# Connectors_and_mechanical.net
KiCad netlist of a schematic drawn in Altium Designer
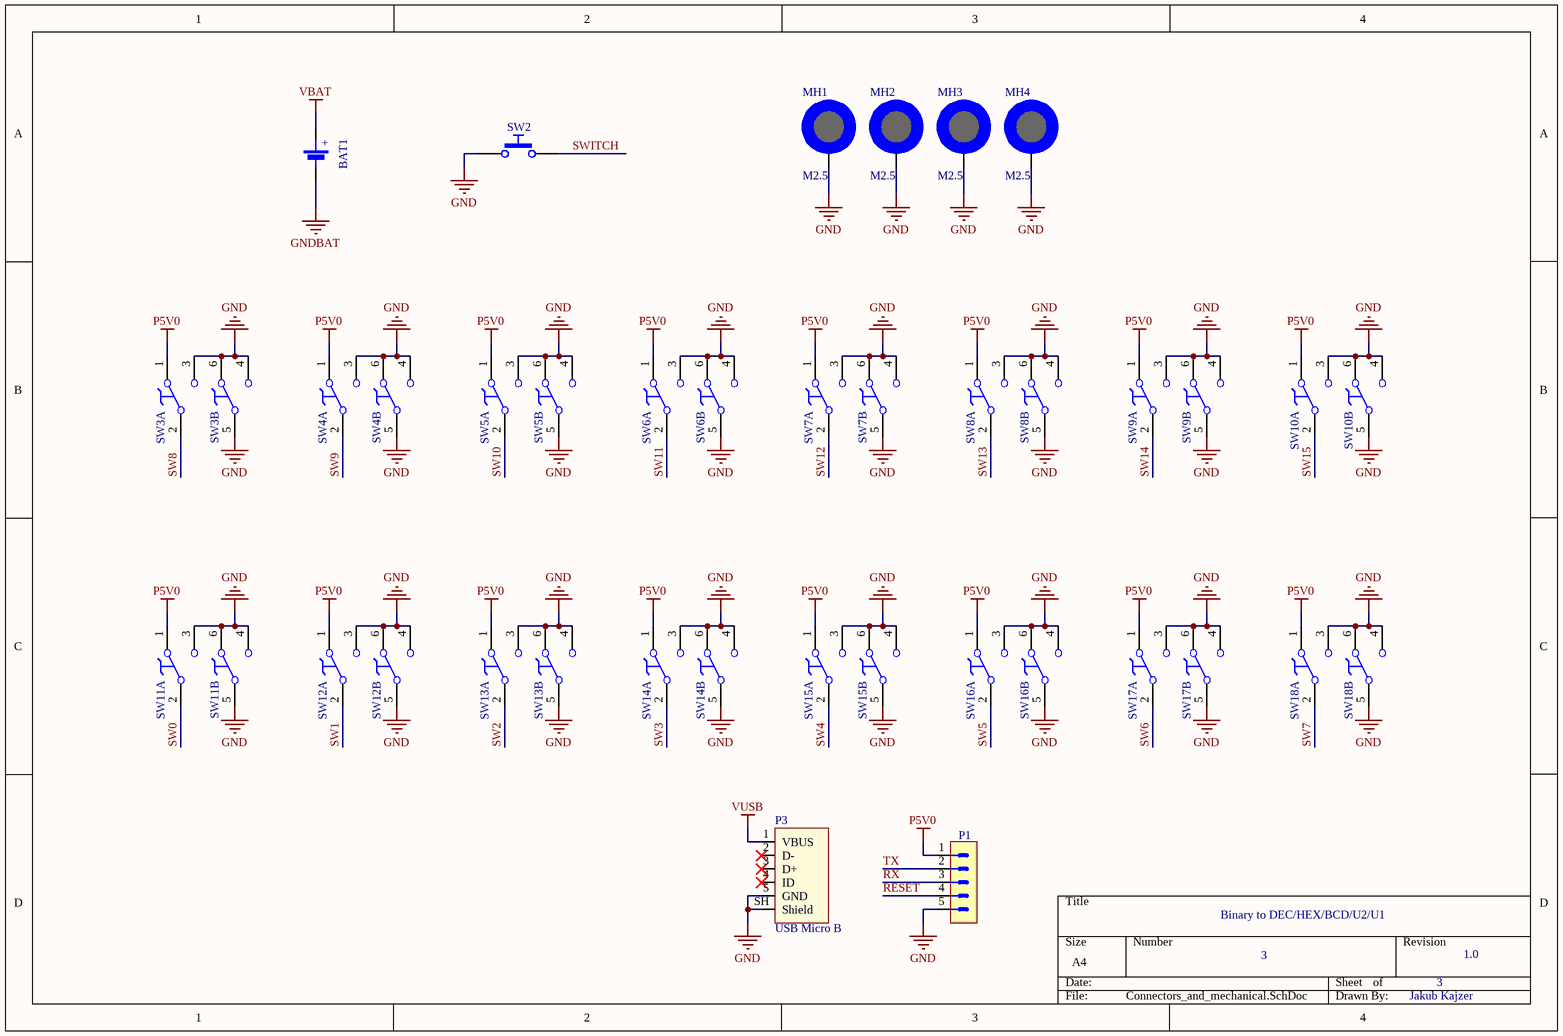
[diagram p0: Connectors_and_mechanical.SchDoc]

(export (version "E")
  (design (tool "Eeschema 10.0.6"))
  (components
    (comp (ref "BAT1")
      (value "~")
      (footprint "18650 Holder")
      (description "18650 Cell Battery Holder")
      (fields
        (field (name "MANUFACTURER") "GENERIC")
        (field (name "MANUFACTURER PART NUMBER") "18650 Holder")
        (field (name "AUTHOR") "JK")
      )
      (libsource (lib "Connectors") (part "BAT-HLD-001"))
    )
    (comp (ref "MH1")
      (value "M2.5")
      (footprint "MH-M2.5_COPPER")
      (description "Mounting hole, M2.5, exposed pad")
      (fields (field (name "AUTHOR") "KB"))
      (libsource (lib "Mechanical And PCB Features") (part "MH"))
    )
    (comp (ref "MH2")
      (value "M2.5")
      (footprint "MH-M2.5_COPPER")
      (description "Mounting hole, M2.5, exposed pad")
      (fields (field (name "AUTHOR") "KB"))
      (libsource (lib "Mechanical And PCB Features") (part "MH"))
    )
    (comp (ref "MH3")
      (value "M2.5")
      (footprint "MH-M2.5_COPPER")
      (description "Mounting hole, M2.5, exposed pad")
      (fields (field (name "AUTHOR") "KB"))
      (libsource (lib "Mechanical And PCB Features") (part "MH"))
    )
    (comp (ref "MH4")
      (value "M2.5")
      (footprint "MH-M2.5_COPPER")
      (description "Mounting hole, M2.5, exposed pad")
      (fields (field (name "AUTHOR") "KB"))
      (libsource (lib "Mechanical And PCB Features") (part "MH"))
    )
    (comp (ref "P1")
      (value "SSW-105-02-G-S")
      (footprint "SAMTEC_SSW-105-02-G-S")
      (description "General Purpose Header: THT, 2.54mm, Female, Straight, Long Lead")
      (fields
        (field (name "MANUFACTURER") "GENERIC")
        (field (name "MANUFACTURER PART NUMBER") "HDR_THT_5X1V_F_2P54MM")
        (field (name "AUTHOR") "UN")
      )
      (libsource (lib "Connectors") (part "Header 5x1"))
    )
    (comp (ref "P3")
      (value "USB Micro B")
      (footprint "USB Micro")
      (description "USB B micro; SMT; PIN: 5; Horizontal; V: USB 2.0")
      (fields
        (field (name "MANUFACTURER") "AMPHENOL")
        (field (name "MANUFACTURER PART NUMBER") "10118192-0001LF")
        (field (name "AUTHOR") "JK")
      )
      (libsource (lib "Connectors") (part "USB_5pin+Shield"))
    )
    (comp (ref "SW2")
      (value "PTS636")
      (footprint "PTS636_SMT_G")
      (description "Tactile Switches Tact 50mA 12VDC, 6.0x3.5, 4.3mm H, 180gf, G leads, No ground pin, Black Actuator")
      (fields
        (field (name "MANUFACTURER") "C&K")
        (field (name "MANUFACTURER PART NUMBER") "PTS636 SM43 SMTR LFS")
        (field (name "AUTHOR") "KB")
      )
      (libsource (lib "Relays And Switches") (part "PB SPST 1NO-2NO"))
    )
    (comp (ref "SW3")
      (value "SS008B")
      (footprint "SS008B-02P-22")
      (description "Switch  2 position; DPDT; 0,3A/30VDC; ON-ON; 50mŁ[")
      (fields
        (field (name "MANUFACTURER") "CANAL ELECTRONIC")
        (field (name "MANUFACTURER PART NUMBER") "SS008B-02P-22")
        (field (name "AUTHOR") "JK")
      )
      (libsource (lib "") (part "SW DPDT 1NC-2C-3NO-4NO-5C-6NC_1"))
    )
    (comp (ref "SW4")
      (value "SS008B")
      (footprint "SS008B-02P-22")
      (description "Switch  2 position; DPDT; 0,3A/30VDC; ON-ON; 50mŁ[")
      (fields
        (field (name "MANUFACTURER") "CANAL ELECTRONIC")
        (field (name "MANUFACTURER PART NUMBER") "SS008B-02P-22")
        (field (name "AUTHOR") "JK")
      )
      (libsource (lib "") (part "SW DPDT 1NC-2C-3NO-4NO-5C-6NC_1"))
    )
    (comp (ref "SW5")
      (value "SS008B")
      (footprint "SS008B-02P-22")
      (description "Switch  2 position; DPDT; 0,3A/30VDC; ON-ON; 50mŁ[")
      (fields
        (field (name "MANUFACTURER") "CANAL ELECTRONIC")
        (field (name "MANUFACTURER PART NUMBER") "SS008B-02P-22")
        (field (name "AUTHOR") "JK")
      )
      (libsource (lib "Relays And Switches") (part "SW DPDT 1NC-2C-3NO-4NO-5C-6NC"))
    )
    (comp (ref "SW6")
      (value "SS008B")
      (footprint "SS008B-02P-22")
      (description "Switch  2 position; DPDT; 0,3A/30VDC; ON-ON; 50mŁ[")
      (fields
        (field (name "MANUFACTURER") "CANAL ELECTRONIC")
        (field (name "MANUFACTURER PART NUMBER") "SS008B-02P-22")
        (field (name "AUTHOR") "JK")
      )
      (libsource (lib "Relays And Switches") (part "SW DPDT 1NC-2C-3NO-4NO-5C-6NC"))
    )
    (comp (ref "SW7")
      (value "SS008B")
      (footprint "SS008B-02P-22")
      (description "Switch  2 position; DPDT; 0,3A/30VDC; ON-ON; 50mŁ[")
      (fields
        (field (name "MANUFACTURER") "CANAL ELECTRONIC")
        (field (name "MANUFACTURER PART NUMBER") "SS008B-02P-22")
        (field (name "AUTHOR") "JK")
      )
      (libsource (lib "") (part "SW DPDT 1NC-2C-3NO-4NO-5C-6NC_1"))
    )
    (comp (ref "SW8")
      (value "SS008B")
      (footprint "SS008B-02P-22")
      (description "Switch  2 position; DPDT; 0,3A/30VDC; ON-ON; 50mŁ[")
      (fields
        (field (name "MANUFACTURER") "CANAL ELECTRONIC")
        (field (name "MANUFACTURER PART NUMBER") "SS008B-02P-22")
        (field (name "AUTHOR") "JK")
      )
      (libsource (lib "Relays And Switches") (part "SW DPDT 1NC-2C-3NO-4NO-5C-6NC"))
    )
    (comp (ref "SW9")
      (value "SS008B")
      (footprint "SS008B-02P-22")
      (description "Switch  2 position; DPDT; 0,3A/30VDC; ON-ON; 50mŁ[")
      (fields
        (field (name "MANUFACTURER") "CANAL ELECTRONIC")
        (field (name "MANUFACTURER PART NUMBER") "SS008B-02P-22")
        (field (name "AUTHOR") "JK")
      )
      (libsource (lib "Relays And Switches") (part "SW DPDT 1NC-2C-3NO-4NO-5C-6NC"))
    )
    (comp (ref "SW10")
      (value "SS008B")
      (footprint "SS008B-02P-22")
      (description "Switch  2 position; DPDT; 0,3A/30VDC; ON-ON; 50mŁ[")
      (fields
        (field (name "MANUFACTURER") "CANAL ELECTRONIC")
        (field (name "MANUFACTURER PART NUMBER") "SS008B-02P-22")
        (field (name "AUTHOR") "JK")
      )
      (libsource (lib "Relays And Switches") (part "SW DPDT 1NC-2C-3NO-4NO-5C-6NC"))
    )
    (comp (ref "SW11")
      (value "SS008B")
      (footprint "SS008B-02P-22")
      (description "Switch  2 position; DPDT; 0,3A/30VDC; ON-ON; 50mŁ[")
      (fields
        (field (name "MANUFACTURER") "CANAL ELECTRONIC")
        (field (name "MANUFACTURER PART NUMBER") "SS008B-02P-22")
        (field (name "AUTHOR") "JK")
      )
      (libsource (lib "Relays And Switches") (part "SW DPDT 1NC-2C-3NO-4NO-5C-6NC"))
    )
    (comp (ref "SW12")
      (value "SS008B")
      (footprint "SS008B-02P-22")
      (description "Switch  2 position; DPDT; 0,3A/30VDC; ON-ON; 50mŁ[")
      (fields
        (field (name "MANUFACTURER") "CANAL ELECTRONIC")
        (field (name "MANUFACTURER PART NUMBER") "SS008B-02P-22")
        (field (name "AUTHOR") "JK")
      )
      (libsource (lib "Relays And Switches") (part "SW DPDT 1NC-2C-3NO-4NO-5C-6NC"))
    )
    (comp (ref "SW13")
      (value "SS008B")
      (footprint "SS008B-02P-22")
      (description "Switch  2 position; DPDT; 0,3A/30VDC; ON-ON; 50mŁ[")
      (fields
        (field (name "MANUFACTURER") "CANAL ELECTRONIC")
        (field (name "MANUFACTURER PART NUMBER") "SS008B-02P-22")
        (field (name "AUTHOR") "JK")
      )
      (libsource (lib "") (part "SW DPDT 1NC-2C-3NO-4NO-5C-6NC_1"))
    )
    (comp (ref "SW14")
      (value "SS008B")
      (footprint "SS008B-02P-22")
      (description "Switch  2 position; DPDT; 0,3A/30VDC; ON-ON; 50mŁ[")
      (fields
        (field (name "MANUFACTURER") "CANAL ELECTRONIC")
        (field (name "MANUFACTURER PART NUMBER") "SS008B-02P-22")
        (field (name "AUTHOR") "JK")
      )
      (libsource (lib "") (part "SW DPDT 1NC-2C-3NO-4NO-5C-6NC_1"))
    )
    (comp (ref "SW15")
      (value "SS008B")
      (footprint "SS008B-02P-22")
      (description "Switch  2 position; DPDT; 0,3A/30VDC; ON-ON; 50mŁ[")
      (fields
        (field (name "MANUFACTURER") "CANAL ELECTRONIC")
        (field (name "MANUFACTURER PART NUMBER") "SS008B-02P-22")
        (field (name "AUTHOR") "JK")
      )
      (libsource (lib "Relays And Switches") (part "SW DPDT 1NC-2C-3NO-4NO-5C-6NC"))
    )
    (comp (ref "SW16")
      (value "SS008B")
      (footprint "SS008B-02P-22")
      (description "Switch  2 position; DPDT; 0,3A/30VDC; ON-ON; 50mŁ[")
      (fields
        (field (name "MANUFACTURER") "CANAL ELECTRONIC")
        (field (name "MANUFACTURER PART NUMBER") "SS008B-02P-22")
        (field (name "AUTHOR") "JK")
      )
      (libsource (lib "Relays And Switches") (part "SW DPDT 1NC-2C-3NO-4NO-5C-6NC"))
    )
    (comp (ref "SW17")
      (value "SS008B")
      (footprint "SS008B-02P-22")
      (description "Switch  2 position; DPDT; 0,3A/30VDC; ON-ON; 50mŁ[")
      (fields
        (field (name "MANUFACTURER") "CANAL ELECTRONIC")
        (field (name "MANUFACTURER PART NUMBER") "SS008B-02P-22")
        (field (name "AUTHOR") "JK")
      )
      (libsource (lib "") (part "SW DPDT 1NC-2C-3NO-4NO-5C-6NC_1"))
    )
    (comp (ref "SW18")
      (value "SS008B")
      (footprint "SS008B-02P-22")
      (description "Switch  2 position; DPDT; 0,3A/30VDC; ON-ON; 50mŁ[")
      (fields
        (field (name "MANUFACTURER") "CANAL ELECTRONIC")
        (field (name "MANUFACTURER PART NUMBER") "SS008B-02P-22")
        (field (name "AUTHOR") "JK")
      )
      (libsource (lib "Relays And Switches") (part "SW DPDT 1NC-2C-3NO-4NO-5C-6NC"))
    )
  )
  (nets
    (net (code "1") (name "/RESET") (class "Default")
      (node (ref "P1") (pin "4") (pinfunction "4_4") (pintype "passive"))
    )
    (net (code "2") (name "/RX") (class "Default")
      (node (ref "P1") (pin "3") (pinfunction "3_3") (pintype "passive"))
    )
    (net (code "3") (name "/SW0") (class "Default")
      (node (ref "SW11") (pin "2") (pinfunction "2_2") (pintype "passive"))
    )
    (net (code "4") (name "/SW1") (class "Default")
      (node (ref "SW12") (pin "2") (pinfunction "2_2") (pintype "passive"))
    )
    (net (code "5") (name "/SW2") (class "Default")
      (node (ref "SW13") (pin "2") (pinfunction "2_2") (pintype "passive"))
    )
    (net (code "6") (name "/SW3") (class "Default")
      (node (ref "SW14") (pin "2") (pinfunction "2_2") (pintype "passive"))
    )
    (net (code "7") (name "/SW4") (class "Default")
      (node (ref "SW15") (pin "2") (pinfunction "2_2") (pintype "passive"))
    )
    (net (code "8") (name "/SW5") (class "Default")
      (node (ref "SW16") (pin "2") (pinfunction "2_2") (pintype "passive"))
    )
    (net (code "9") (name "/SW6") (class "Default")
      (node (ref "SW17") (pin "2") (pinfunction "2_2") (pintype "passive"))
    )
    (net (code "10") (name "/SW7") (class "Default")
      (node (ref "SW18") (pin "2") (pinfunction "2_2") (pintype "passive"))
    )
    (net (code "11") (name "/SW8") (class "Default")
      (node (ref "SW3") (pin "2") (pinfunction "2_2") (pintype "passive"))
    )
    (net (code "12") (name "/SW9") (class "Default")
      (node (ref "SW4") (pin "2") (pinfunction "2_2") (pintype "passive"))
    )
    (net (code "13") (name "/SW10") (class "Default")
      (node (ref "SW5") (pin "2") (pinfunction "2_2") (pintype "passive"))
    )
    (net (code "14") (name "/SW11") (class "Default")
      (node (ref "SW6") (pin "2") (pinfunction "2_2") (pintype "passive"))
    )
    (net (code "15") (name "/SW12") (class "Default")
      (node (ref "SW7") (pin "2") (pinfunction "2_2") (pintype "passive"))
    )
    (net (code "16") (name "/SW13") (class "Default")
      (node (ref "SW8") (pin "2") (pinfunction "2_2") (pintype "passive"))
    )
    (net (code "17") (name "/SW14") (class "Default")
      (node (ref "SW9") (pin "2") (pinfunction "2_2") (pintype "passive"))
    )
    (net (code "18") (name "/SW15") (class "Default")
      (node (ref "SW10") (pin "2") (pinfunction "2_2") (pintype "passive"))
    )
    (net (code "19") (name "/SWITCH") (class "Default")
      (node (ref "SW2") (pin "2") (pinfunction "2_2") (pintype "passive"))
    )
    (net (code "20") (name "/TX") (class "Default")
      (node (ref "P1") (pin "2") (pinfunction "2_2") (pintype "passive"))
    )
    (net (code "21") (name "GND") (class "Default")
      (node (ref "MH1") (pin "MH") (pinfunction "MH_MH") (pintype "passive"))
      (node (ref "MH2") (pin "MH") (pinfunction "MH_MH") (pintype "passive"))
      (node (ref "MH3") (pin "MH") (pinfunction "MH_MH") (pintype "passive"))
      (node (ref "MH4") (pin "MH") (pinfunction "MH_MH") (pintype "passive"))
      (node (ref "P1") (pin "5") (pinfunction "5_5") (pintype "passive"))
      (node (ref "P3") (pin "5") (pinfunction "GND_5") (pintype "power_in"))
      (node (ref "P3") (pin "SH") (pinfunction "Shield_SH") (pintype "passive"))
      (node (ref "SW10") (pin "3") (pinfunction "3_3") (pintype "passive"))
      (node (ref "SW10") (pin "4") (pinfunction "4_4") (pintype "passive"))
      (node (ref "SW10") (pin "5") (pinfunction "5_5") (pintype "passive"))
      (node (ref "SW10") (pin "6") (pinfunction "6_6") (pintype "passive"))
      (node (ref "SW11") (pin "3") (pinfunction "3_3") (pintype "passive"))
      (node (ref "SW11") (pin "4") (pinfunction "4_4") (pintype "passive"))
      (node (ref "SW11") (pin "5") (pinfunction "5_5") (pintype "passive"))
      (node (ref "SW11") (pin "6") (pinfunction "6_6") (pintype "passive"))
      (node (ref "SW12") (pin "3") (pinfunction "3_3") (pintype "passive"))
      (node (ref "SW12") (pin "4") (pinfunction "4_4") (pintype "passive"))
      (node (ref "SW12") (pin "5") (pinfunction "5_5") (pintype "passive"))
      (node (ref "SW12") (pin "6") (pinfunction "6_6") (pintype "passive"))
      (node (ref "SW13") (pin "3") (pinfunction "3_3") (pintype "passive"))
      (node (ref "SW13") (pin "4") (pinfunction "4_4") (pintype "passive"))
      (node (ref "SW13") (pin "5") (pinfunction "5_5") (pintype "passive"))
      (node (ref "SW13") (pin "6") (pinfunction "6_6") (pintype "passive"))
      (node (ref "SW14") (pin "3") (pinfunction "3_3") (pintype "passive"))
      (node (ref "SW14") (pin "4") (pinfunction "4_4") (pintype "passive"))
      (node (ref "SW14") (pin "5") (pinfunction "5_5") (pintype "passive"))
      (node (ref "SW14") (pin "6") (pinfunction "6_6") (pintype "passive"))
      (node (ref "SW15") (pin "3") (pinfunction "3_3") (pintype "passive"))
      (node (ref "SW15") (pin "4") (pinfunction "4_4") (pintype "passive"))
      (node (ref "SW15") (pin "5") (pinfunction "5_5") (pintype "passive"))
      (node (ref "SW15") (pin "6") (pinfunction "6_6") (pintype "passive"))
      (node (ref "SW16") (pin "3") (pinfunction "3_3") (pintype "passive"))
      (node (ref "SW16") (pin "4") (pinfunction "4_4") (pintype "passive"))
      (node (ref "SW16") (pin "5") (pinfunction "5_5") (pintype "passive"))
      (node (ref "SW16") (pin "6") (pinfunction "6_6") (pintype "passive"))
      (node (ref "SW17") (pin "3") (pinfunction "3_3") (pintype "passive"))
      (node (ref "SW17") (pin "4") (pinfunction "4_4") (pintype "passive"))
      (node (ref "SW17") (pin "5") (pinfunction "5_5") (pintype "passive"))
      (node (ref "SW17") (pin "6") (pinfunction "6_6") (pintype "passive"))
      (node (ref "SW18") (pin "3") (pinfunction "3_3") (pintype "passive"))
      (node (ref "SW18") (pin "4") (pinfunction "4_4") (pintype "passive"))
      (node (ref "SW18") (pin "5") (pinfunction "5_5") (pintype "passive"))
      (node (ref "SW18") (pin "6") (pinfunction "6_6") (pintype "passive"))
      (node (ref "SW2") (pin "1") (pinfunction "1_1") (pintype "passive"))
      (node (ref "SW3") (pin "3") (pinfunction "3_3") (pintype "passive"))
      (node (ref "SW3") (pin "4") (pinfunction "4_4") (pintype "passive"))
      (node (ref "SW3") (pin "5") (pinfunction "5_5") (pintype "passive"))
      (node (ref "SW3") (pin "6") (pinfunction "6_6") (pintype "passive"))
      (node (ref "SW4") (pin "3") (pinfunction "3_3") (pintype "passive"))
      (node (ref "SW4") (pin "4") (pinfunction "4_4") (pintype "passive"))
      (node (ref "SW4") (pin "5") (pinfunction "5_5") (pintype "passive"))
      (node (ref "SW4") (pin "6") (pinfunction "6_6") (pintype "passive"))
      (node (ref "SW5") (pin "3") (pinfunction "3_3") (pintype "passive"))
      (node (ref "SW5") (pin "4") (pinfunction "4_4") (pintype "passive"))
      (node (ref "SW5") (pin "5") (pinfunction "5_5") (pintype "passive"))
      (node (ref "SW5") (pin "6") (pinfunction "6_6") (pintype "passive"))
      (node (ref "SW6") (pin "3") (pinfunction "3_3") (pintype "passive"))
      (node (ref "SW6") (pin "4") (pinfunction "4_4") (pintype "passive"))
      (node (ref "SW6") (pin "5") (pinfunction "5_5") (pintype "passive"))
      (node (ref "SW6") (pin "6") (pinfunction "6_6") (pintype "passive"))
      (node (ref "SW7") (pin "3") (pinfunction "3_3") (pintype "passive"))
      (node (ref "SW7") (pin "4") (pinfunction "4_4") (pintype "passive"))
      (node (ref "SW7") (pin "5") (pinfunction "5_5") (pintype "passive"))
      (node (ref "SW7") (pin "6") (pinfunction "6_6") (pintype "passive"))
      (node (ref "SW8") (pin "3") (pinfunction "3_3") (pintype "passive"))
      (node (ref "SW8") (pin "4") (pinfunction "4_4") (pintype "passive"))
      (node (ref "SW8") (pin "5") (pinfunction "5_5") (pintype "passive"))
      (node (ref "SW8") (pin "6") (pinfunction "6_6") (pintype "passive"))
      (node (ref "SW9") (pin "3") (pinfunction "3_3") (pintype "passive"))
      (node (ref "SW9") (pin "4") (pinfunction "4_4") (pintype "passive"))
      (node (ref "SW9") (pin "5") (pinfunction "5_5") (pintype "passive"))
      (node (ref "SW9") (pin "6") (pinfunction "6_6") (pintype "passive"))
    )
    (net (code "22") (name "GNDBAT") (class "Default")
      (node (ref "BAT1") (pin "1") (pinfunction "MINUS_1") (pintype "power_in"))
    )
    (net (code "23") (name "P5V0") (class "Default")
      (node (ref "P1") (pin "1") (pinfunction "1_1") (pintype "passive"))
      (node (ref "SW10") (pin "1") (pinfunction "1_1") (pintype "passive"))
      (node (ref "SW11") (pin "1") (pinfunction "1_1") (pintype "passive"))
      (node (ref "SW12") (pin "1") (pinfunction "1_1") (pintype "passive"))
      (node (ref "SW13") (pin "1") (pinfunction "1_1") (pintype "passive"))
      (node (ref "SW14") (pin "1") (pinfunction "1_1") (pintype "passive"))
      (node (ref "SW15") (pin "1") (pinfunction "1_1") (pintype "passive"))
      (node (ref "SW16") (pin "1") (pinfunction "1_1") (pintype "passive"))
      (node (ref "SW17") (pin "1") (pinfunction "1_1") (pintype "passive"))
      (node (ref "SW18") (pin "1") (pinfunction "1_1") (pintype "passive"))
      (node (ref "SW3") (pin "1") (pinfunction "1_1") (pintype "passive"))
      (node (ref "SW4") (pin "1") (pinfunction "1_1") (pintype "passive"))
      (node (ref "SW5") (pin "1") (pinfunction "1_1") (pintype "passive"))
      (node (ref "SW6") (pin "1") (pinfunction "1_1") (pintype "passive"))
      (node (ref "SW7") (pin "1") (pinfunction "1_1") (pintype "passive"))
      (node (ref "SW8") (pin "1") (pinfunction "1_1") (pintype "passive"))
      (node (ref "SW9") (pin "1") (pinfunction "1_1") (pintype "passive"))
    )
    (net (code "24") (name "VBAT") (class "Default")
      (node (ref "BAT1") (pin "2") (pinfunction "PLUS_2") (pintype "power_in"))
    )
    (net (code "25") (name "VUSB") (class "Default")
      (node (ref "P3") (pin "1") (pinfunction "VBUS_1") (pintype "power_in"))
    )
    (net (code "26") (name "unconnected-(P3-D+-Pad3)") (class "Default")
      (node (ref "P3") (pin "3") (pinfunction "D+_3") (pintype "bidirectional+no_connect"))
    )
    (net (code "27") (name "unconnected-(P3-D--Pad2)") (class "Default")
      (node (ref "P3") (pin "2") (pinfunction "D-_2") (pintype "bidirectional+no_connect"))
    )
    (net (code "28") (name "unconnected-(P3-ID-Pad4)") (class "Default")
      (node (ref "P3") (pin "4") (pinfunction "ID_4") (pintype "bidirectional+no_connect"))
    )
  )
)
